# untitled.net
KiCad netlist of a schematic drawn in EAGLE
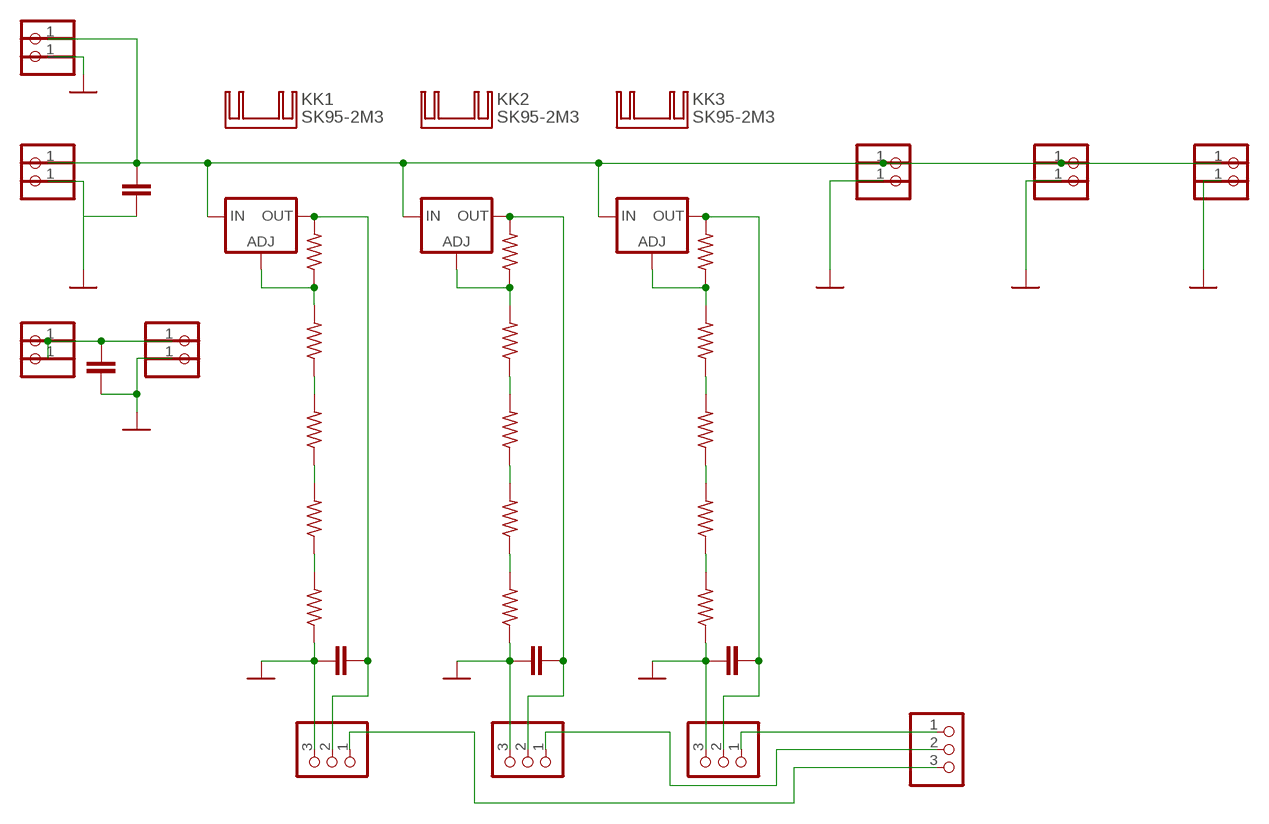
[diagram p0: schematic, sheet 1]

(export (version "E")
  (design (tool "Eeschema 10.0.6"))
  (components
    (comp (ref "5V")
      (value "PINHD-1X1")
      (footprint "eagle-import:1X01")
      (libsource (lib "eagle-import") (part "PINHD-1X1"))
    )
    (comp (ref "5V+")
      (value "PINHD-1X1")
      (footprint "eagle-import:1X01")
      (libsource (lib "eagle-import") (part "PINHD-1X1"))
    )
    (comp (ref "5V-")
      (value "PINHD-1X1")
      (footprint "eagle-import:1X01")
      (libsource (lib "eagle-import") (part "PINHD-1X1"))
    )
    (comp (ref "5VV")
      (value "PINHD-1X1")
      (footprint "eagle-import:1X01")
      (libsource (lib "eagle-import") (part "PINHD-1X1"))
    )
    (comp (ref "BATTERY+")
      (value "PINHD-1X1")
      (footprint "eagle-import:1X01")
      (libsource (lib "eagle-import") (part "PINHD-1X1"))
    )
    (comp (ref "BATTERY-")
      (value "PINHD-1X1")
      (footprint "eagle-import:1X01")
      (libsource (lib "eagle-import") (part "PINHD-1X1"))
    )
    (comp (ref "C1")
      (value "C-EU025-050X050")
      (footprint "eagle-import:C025-050X050")
      (libsource (lib "eagle-import") (part "C-EU025-050X050"))
    )
    (comp (ref "C2")
      (value "C-EU025-050X050")
      (footprint "eagle-import:C025-050X050")
      (libsource (lib "eagle-import") (part "C-EU025-050X050"))
    )
    (comp (ref "C3")
      (value "C-EU025-050X050")
      (footprint "eagle-import:C025-050X050")
      (libsource (lib "eagle-import") (part "C-EU025-050X050"))
    )
    (comp (ref "C4")
      (value "C-EU025-050X050")
      (footprint "eagle-import:C025-050X050")
      (libsource (lib "eagle-import") (part "C-EU025-050X050"))
    )
    (comp (ref "C5")
      (value "C-EU025-050X050")
      (footprint "eagle-import:C025-050X050")
      (libsource (lib "eagle-import") (part "C-EU025-050X050"))
    )
    (comp (ref "D1+")
      (value "PINHD-1X1")
      (footprint "eagle-import:1X01")
      (libsource (lib "eagle-import") (part "PINHD-1X1"))
    )
    (comp (ref "D1-")
      (value "PINHD-1X1")
      (footprint "eagle-import:1X01")
      (libsource (lib "eagle-import") (part "PINHD-1X1"))
    )
    (comp (ref "D2+")
      (value "PINHD-1X1")
      (footprint "eagle-import:1X01")
      (libsource (lib "eagle-import") (part "PINHD-1X1"))
    )
    (comp (ref "D2-")
      (value "PINHD-1X1")
      (footprint "eagle-import:1X01")
      (libsource (lib "eagle-import") (part "PINHD-1X1"))
    )
    (comp (ref "D3+")
      (value "PINHD-1X1")
      (footprint "eagle-import:1X01")
      (libsource (lib "eagle-import") (part "PINHD-1X1"))
    )
    (comp (ref "D3-")
      (value "PINHD-1X1")
      (footprint "eagle-import:1X01")
      (libsource (lib "eagle-import") (part "PINHD-1X1"))
    )
    (comp (ref "IC4")
      (value "LM317TS")
      (footprint "eagle-import:317TS")
      (libsource (lib "eagle-import") (part "LM317TS"))
    )
    (comp (ref "IC5")
      (value "LM317TS")
      (footprint "eagle-import:317TS")
      (libsource (lib "eagle-import") (part "LM317TS"))
    )
    (comp (ref "IC6")
      (value "LM317TS")
      (footprint "eagle-import:317TS")
      (libsource (lib "eagle-import") (part "LM317TS"))
    )
    (comp (ref "JP1")
      (value "PINHD-1X3")
      (footprint "eagle-import:1X03")
      (libsource (lib "eagle-import") (part "PINHD-1X3"))
    )
    (comp (ref "JP2")
      (value "PINHD-1X3")
      (footprint "eagle-import:1X03")
      (libsource (lib "eagle-import") (part "PINHD-1X3"))
    )
    (comp (ref "JP3")
      (value "PINHD-1X3")
      (footprint "eagle-import:1X03")
      (libsource (lib "eagle-import") (part "PINHD-1X3"))
    )
    (comp (ref "JP6")
      (value "PINHD-1X3")
      (footprint "eagle-import:1X03")
      (libsource (lib "eagle-import") (part "PINHD-1X3"))
    )
    (comp (ref "KK1")
      (value "SK95-2M3")
      (footprint "eagle-import:SK95-2M3")
      (libsource (lib "eagle-import") (part "SK95-2M3"))
    )
    (comp (ref "KK2")
      (value "SK95-2M3")
      (footprint "eagle-import:SK95-2M3")
      (libsource (lib "eagle-import") (part "SK95-2M3"))
    )
    (comp (ref "KK3")
      (value "SK95-2M3")
      (footprint "eagle-import:SK95-2M3")
      (libsource (lib "eagle-import") (part "SK95-2M3"))
    )
    (comp (ref "R1")
      (value "R-US_0207/10")
      (footprint "eagle-import:0207_10")
      (libsource (lib "eagle-import") (part "R-US_0207/10"))
    )
    (comp (ref "R2")
      (value "R-US_0207/10")
      (footprint "eagle-import:0207_10")
      (libsource (lib "eagle-import") (part "R-US_0207/10"))
    )
    (comp (ref "R5")
      (value "R-US_0207/10")
      (footprint "eagle-import:0207_10")
      (libsource (lib "eagle-import") (part "R-US_0207/10"))
    )
    (comp (ref "R6")
      (value "R-US_0207/10")
      (footprint "eagle-import:0207_10")
      (libsource (lib "eagle-import") (part "R-US_0207/10"))
    )
    (comp (ref "R7")
      (value "R-US_0207/10")
      (footprint "eagle-import:0207_10")
      (libsource (lib "eagle-import") (part "R-US_0207/10"))
    )
    (comp (ref "R8")
      (value "R-US_0207/10")
      (footprint "eagle-import:0207_10")
      (libsource (lib "eagle-import") (part "R-US_0207/10"))
    )
    (comp (ref "R9")
      (value "R-US_0207/10")
      (footprint "eagle-import:0207_10")
      (libsource (lib "eagle-import") (part "R-US_0207/10"))
    )
    (comp (ref "R10")
      (value "R-US_0207/10")
      (footprint "eagle-import:0207_10")
      (libsource (lib "eagle-import") (part "R-US_0207/10"))
    )
    (comp (ref "R11")
      (value "R-US_0207/10")
      (footprint "eagle-import:0207_10")
      (libsource (lib "eagle-import") (part "R-US_0207/10"))
    )
    (comp (ref "R12")
      (value "R-US_0207/10")
      (footprint "eagle-import:0207_10")
      (libsource (lib "eagle-import") (part "R-US_0207/10"))
    )
    (comp (ref "R13")
      (value "R-US_0207/10")
      (footprint "eagle-import:0207_10")
      (libsource (lib "eagle-import") (part "R-US_0207/10"))
    )
    (comp (ref "R14")
      (value "R-US_0207/10")
      (footprint "eagle-import:0207_10")
      (libsource (lib "eagle-import") (part "R-US_0207/10"))
    )
    (comp (ref "R15")
      (value "R-US_0207/10")
      (footprint "eagle-import:0207_10")
      (libsource (lib "eagle-import") (part "R-US_0207/10"))
    )
    (comp (ref "R16")
      (value "R-US_0207/10")
      (footprint "eagle-import:0207_10")
      (libsource (lib "eagle-import") (part "R-US_0207/10"))
    )
    (comp (ref "R17")
      (value "R-US_0207/10")
      (footprint "eagle-import:0207_10")
      (libsource (lib "eagle-import") (part "R-US_0207/10"))
    )
    (comp (ref "SOLAR+")
      (value "PINHD-1X1")
      (footprint "eagle-import:1X01")
      (libsource (lib "eagle-import") (part "PINHD-1X1"))
    )
    (comp (ref "SOLAR-")
      (value "PINHD-1X1")
      (footprint "eagle-import:1X01")
      (libsource (lib "eagle-import") (part "PINHD-1X1"))
    )
  )
  (nets
    (net (code "1") (name "GND") (class "Default")
      (node (ref "5V-") (pin "1") (pinfunction "1_1") (pintype "passive"))
      (node (ref "BATTERY-") (pin "1") (pinfunction "1_1") (pintype "passive"))
      (node (ref "C1") (pin "1") (pinfunction "1_1") (pintype "passive"))
      (node (ref "C2") (pin "1") (pinfunction "1_1") (pintype "passive"))
      (node (ref "C3") (pin "1") (pinfunction "1_1") (pintype "passive"))
      (node (ref "C4") (pin "2") (pinfunction "2_2") (pintype "passive"))
      (node (ref "C5") (pin "2") (pinfunction "2_2") (pintype "passive"))
      (node (ref "D1-") (pin "1") (pinfunction "1_1") (pintype "passive"))
      (node (ref "D2-") (pin "1") (pinfunction "1_1") (pintype "passive"))
      (node (ref "D3-") (pin "1") (pinfunction "1_1") (pintype "passive"))
      (node (ref "JP1") (pin "3") (pinfunction "3_3") (pintype "passive"))
      (node (ref "JP2") (pin "3") (pinfunction "3_3") (pintype "passive"))
      (node (ref "JP3") (pin "3") (pinfunction "3_3") (pintype "passive"))
      (node (ref "R13") (pin "1") (pinfunction "1_1") (pintype "passive"))
      (node (ref "R17") (pin "1") (pinfunction "1_1") (pintype "passive"))
      (node (ref "R8") (pin "1") (pinfunction "1_1") (pintype "passive"))
      (node (ref "SOLAR-") (pin "1") (pinfunction "1_1") (pintype "passive"))
    )
    (net (code "2") (name "Net-(5V+-Pad1)") (class "Default")
      (node (ref "5V") (pin "1") (pinfunction "1_1") (pintype "passive"))
      (node (ref "5V+") (pin "1") (pinfunction "1_1") (pintype "passive"))
      (node (ref "5VV") (pin "1") (pinfunction "1_1") (pintype "passive"))
      (node (ref "C5") (pin "1") (pinfunction "1_1") (pintype "passive"))
    )
    (net (code "3") (name "Net-(IC4-ADJ)") (class "Default")
      (node (ref "IC4") (pin "1") (pinfunction "ADJ_1") (pintype "input"))
      (node (ref "R10") (pin "1") (pinfunction "1_1") (pintype "passive"))
      (node (ref "R9") (pin "2") (pinfunction "2_2") (pintype "passive"))
    )
    (net (code "4") (name "Net-(IC4-IN)") (class "Default")
      (node (ref "BATTERY+") (pin "1") (pinfunction "1_1") (pintype "passive"))
      (node (ref "C4") (pin "1") (pinfunction "1_1") (pintype "passive"))
      (node (ref "D1+") (pin "1") (pinfunction "1_1") (pintype "passive"))
      (node (ref "D2+") (pin "1") (pinfunction "1_1") (pintype "passive"))
      (node (ref "D3+") (pin "1") (pinfunction "1_1") (pintype "passive"))
      (node (ref "IC4") (pin "3") (pinfunction "IN_3") (pintype "input"))
      (node (ref "IC5") (pin "3") (pinfunction "IN_3") (pintype "input"))
      (node (ref "IC6") (pin "3") (pinfunction "IN_3") (pintype "input"))
      (node (ref "SOLAR+") (pin "1") (pinfunction "1_1") (pintype "passive"))
    )
    (net (code "5") (name "Net-(IC4-OUT)") (class "Default")
      (node (ref "C1") (pin "2") (pinfunction "2_2") (pintype "passive"))
      (node (ref "IC4") (pin "2") (pinfunction "OUT_2") (pintype "passive"))
      (node (ref "JP2") (pin "2") (pinfunction "2_2") (pintype "passive"))
      (node (ref "R10") (pin "2") (pinfunction "2_2") (pintype "passive"))
    )
    (net (code "6") (name "Net-(IC5-ADJ)") (class "Default")
      (node (ref "IC5") (pin "1") (pinfunction "ADJ_1") (pintype "input"))
      (node (ref "R14") (pin "2") (pinfunction "2_2") (pintype "passive"))
      (node (ref "R5") (pin "1") (pinfunction "1_1") (pintype "passive"))
    )
    (net (code "7") (name "Net-(IC5-OUT)") (class "Default")
      (node (ref "C3") (pin "2") (pinfunction "2_2") (pintype "passive"))
      (node (ref "IC5") (pin "2") (pinfunction "OUT_2") (pintype "passive"))
      (node (ref "JP3") (pin "2") (pinfunction "2_2") (pintype "passive"))
      (node (ref "R5") (pin "2") (pinfunction "2_2") (pintype "passive"))
    )
    (net (code "8") (name "Net-(IC6-ADJ)") (class "Default")
      (node (ref "IC6") (pin "1") (pinfunction "ADJ_1") (pintype "input"))
      (node (ref "R1") (pin "2") (pinfunction "2_2") (pintype "passive"))
      (node (ref "R2") (pin "1") (pinfunction "1_1") (pintype "passive"))
    )
    (net (code "9") (name "Net-(IC6-OUT)") (class "Default")
      (node (ref "C2") (pin "2") (pinfunction "2_2") (pintype "passive"))
      (node (ref "IC6") (pin "2") (pinfunction "OUT_2") (pintype "passive"))
      (node (ref "JP1") (pin "2") (pinfunction "2_2") (pintype "passive"))
      (node (ref "R2") (pin "2") (pinfunction "2_2") (pintype "passive"))
    )
    (net (code "10") (name "Net-(JP1-Pad1)") (class "Default")
      (node (ref "JP1") (pin "1") (pinfunction "1_1") (pintype "passive"))
      (node (ref "JP6") (pin "2") (pinfunction "2_2") (pintype "passive"))
    )
    (net (code "11") (name "Net-(JP2-Pad1)") (class "Default")
      (node (ref "JP2") (pin "1") (pinfunction "1_1") (pintype "passive"))
      (node (ref "JP6") (pin "3") (pinfunction "3_3") (pintype "passive"))
    )
    (net (code "12") (name "Net-(JP3-Pad1)") (class "Default")
      (node (ref "JP3") (pin "1") (pinfunction "1_1") (pintype "passive"))
      (node (ref "JP6") (pin "1") (pinfunction "1_1") (pintype "passive"))
    )
    (net (code "13") (name "Net-(R1-Pad1)") (class "Default")
      (node (ref "R1") (pin "1") (pinfunction "1_1") (pintype "passive"))
      (node (ref "R6") (pin "2") (pinfunction "2_2") (pintype "passive"))
    )
    (net (code "14") (name "Net-(R6-Pad1)") (class "Default")
      (node (ref "R6") (pin "1") (pinfunction "1_1") (pintype "passive"))
      (node (ref "R7") (pin "2") (pinfunction "2_2") (pintype "passive"))
    )
    (net (code "15") (name "Net-(R7-Pad1)") (class "Default")
      (node (ref "R7") (pin "1") (pinfunction "1_1") (pintype "passive"))
      (node (ref "R8") (pin "2") (pinfunction "2_2") (pintype "passive"))
    )
    (net (code "16") (name "Net-(R11-Pad1)") (class "Default")
      (node (ref "R11") (pin "1") (pinfunction "1_1") (pintype "passive"))
      (node (ref "R12") (pin "2") (pinfunction "2_2") (pintype "passive"))
    )
    (net (code "17") (name "Net-(R11-Pad2)") (class "Default")
      (node (ref "R11") (pin "2") (pinfunction "2_2") (pintype "passive"))
      (node (ref "R9") (pin "1") (pinfunction "1_1") (pintype "passive"))
    )
    (net (code "18") (name "Net-(R12-Pad1)") (class "Default")
      (node (ref "R12") (pin "1") (pinfunction "1_1") (pintype "passive"))
      (node (ref "R13") (pin "2") (pinfunction "2_2") (pintype "passive"))
    )
    (net (code "19") (name "Net-(R14-Pad1)") (class "Default")
      (node (ref "R14") (pin "1") (pinfunction "1_1") (pintype "passive"))
      (node (ref "R15") (pin "2") (pinfunction "2_2") (pintype "passive"))
    )
    (net (code "20") (name "Net-(R15-Pad1)") (class "Default")
      (node (ref "R15") (pin "1") (pinfunction "1_1") (pintype "passive"))
      (node (ref "R16") (pin "2") (pinfunction "2_2") (pintype "passive"))
    )
    (net (code "21") (name "Net-(R16-Pad1)") (class "Default")
      (node (ref "R16") (pin "1") (pinfunction "1_1") (pintype "passive"))
      (node (ref "R17") (pin "2") (pinfunction "2_2") (pintype "passive"))
    )
  )
)
